# HVAC8V2.net
KiCad netlist of a schematic drawn in EAGLE
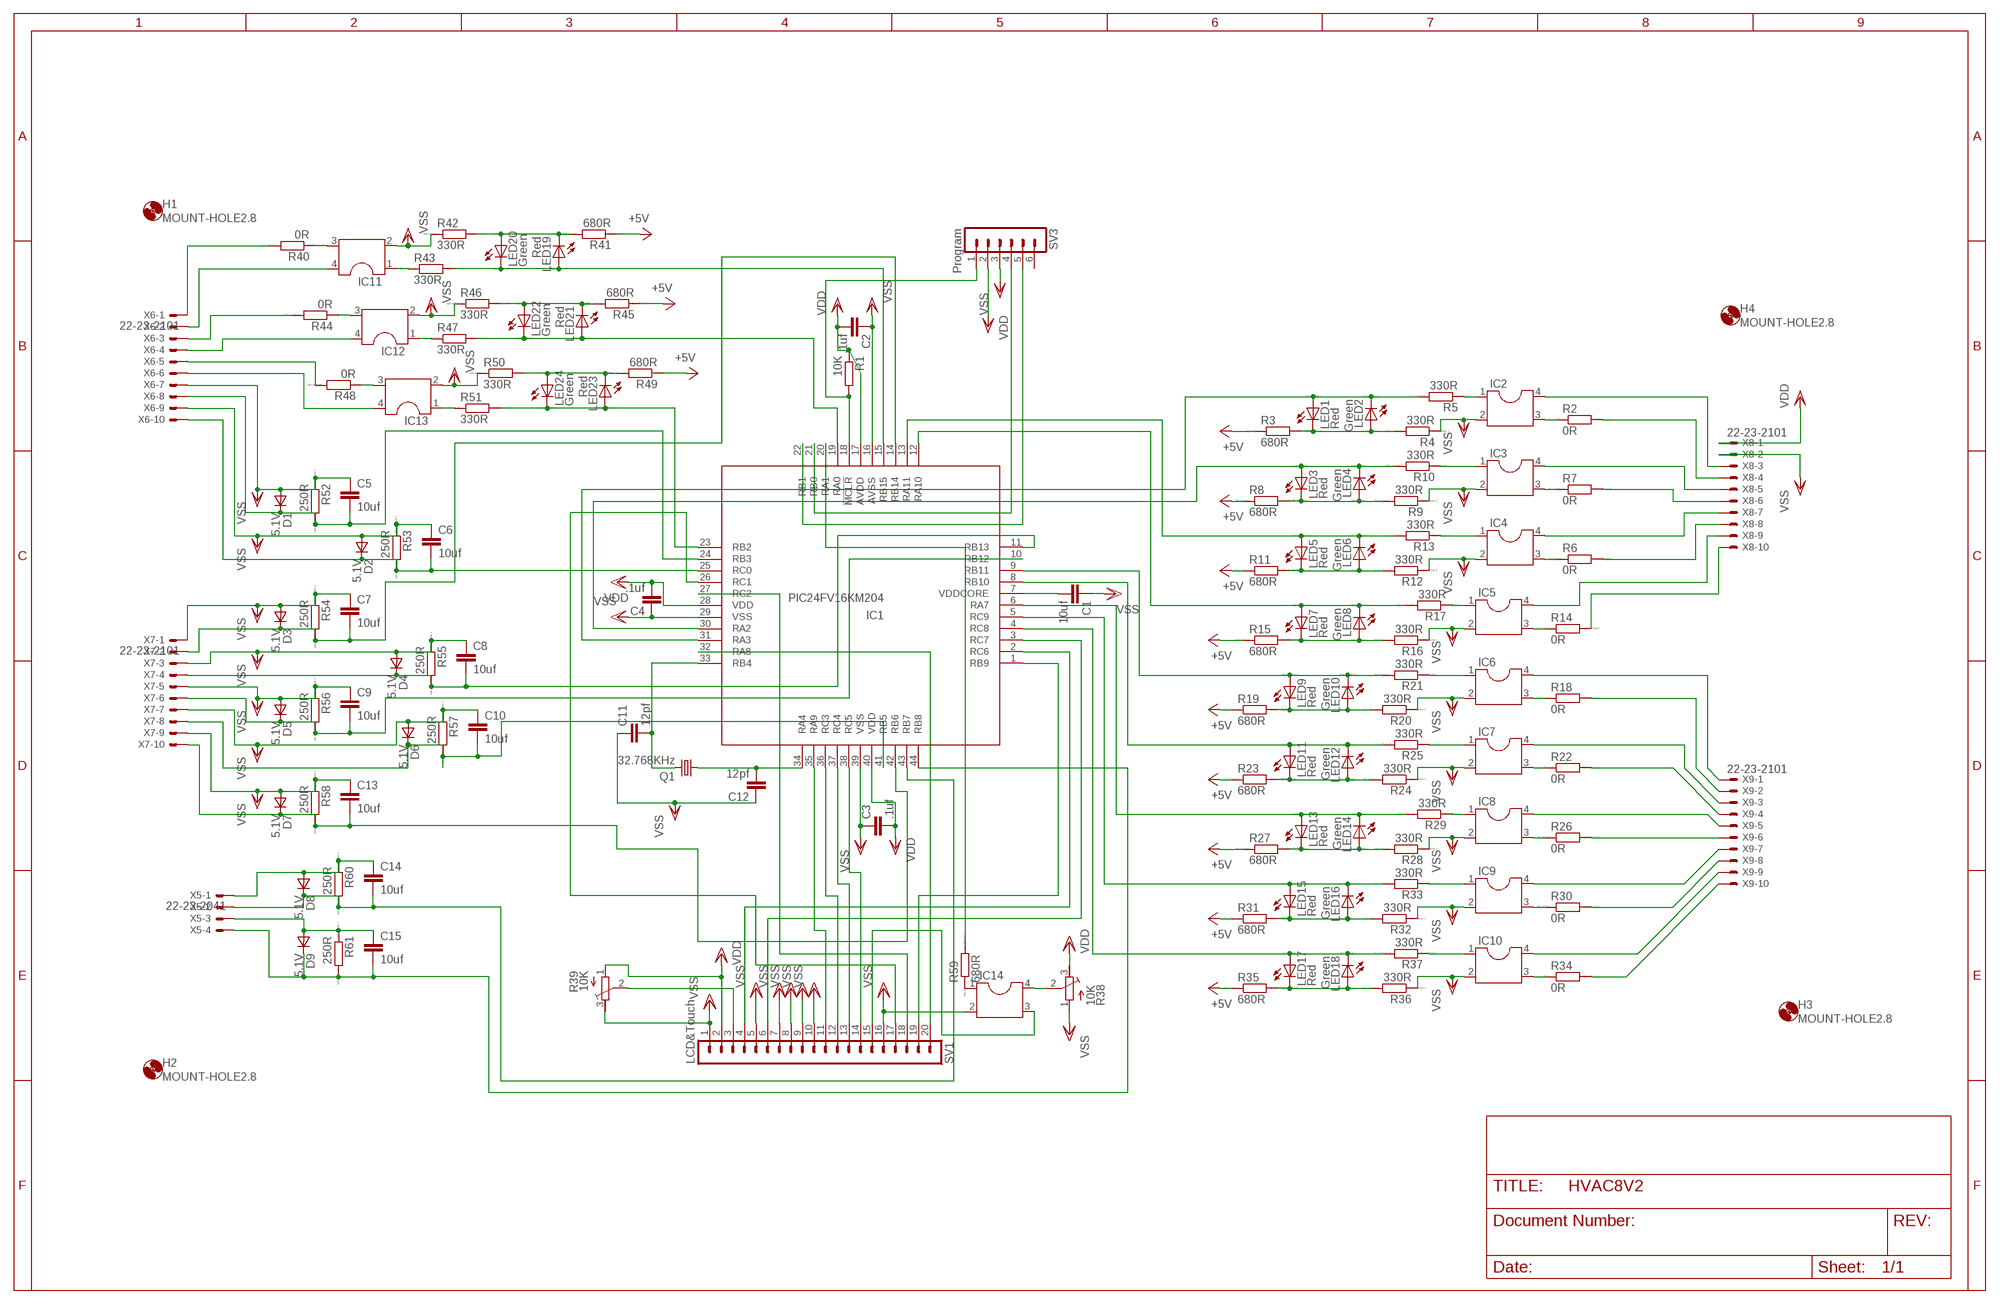
[diagram p0: schematic, sheet 1]

(export (version "E")
  (design (tool "Eeschema 10.0.6"))
  (components
    (comp (ref "C1")
      (value "10uf")
      (footprint "eagle-import:C1206")
      (libsource (lib "eagle-import") (part "C-EUC1206"))
    )
    (comp (ref "C2")
      (value ".1uf")
      (footprint "eagle-import:C1206")
      (libsource (lib "eagle-import") (part "C-EUC1206"))
    )
    (comp (ref "C3")
      (value ".1uf")
      (footprint "eagle-import:C1206")
      (libsource (lib "eagle-import") (part "C-EUC1206"))
    )
    (comp (ref "C4")
      (value ".1uf")
      (footprint "eagle-import:C1206")
      (libsource (lib "eagle-import") (part "C-EUC1206"))
    )
    (comp (ref "C5")
      (value "10uf")
      (footprint "eagle-import:C1206")
      (libsource (lib "eagle-import") (part "C-EUC1206"))
    )
    (comp (ref "C6")
      (value "10uf")
      (footprint "eagle-import:C1206")
      (libsource (lib "eagle-import") (part "C-EUC1206"))
    )
    (comp (ref "C7")
      (value "10uf")
      (footprint "eagle-import:C1206")
      (libsource (lib "eagle-import") (part "C-EUC1206"))
    )
    (comp (ref "C8")
      (value "10uf")
      (footprint "eagle-import:C1206")
      (libsource (lib "eagle-import") (part "C-EUC1206"))
    )
    (comp (ref "C9")
      (value "10uf")
      (footprint "eagle-import:C1206")
      (libsource (lib "eagle-import") (part "C-EUC1206"))
    )
    (comp (ref "C10")
      (value "10uf")
      (footprint "eagle-import:C1206")
      (libsource (lib "eagle-import") (part "C-EUC1206"))
    )
    (comp (ref "C11")
      (value "12pf")
      (footprint "eagle-import:C0603")
      (libsource (lib "eagle-import") (part "C-EUC0603"))
    )
    (comp (ref "C12")
      (value "12pf")
      (footprint "eagle-import:C0603")
      (libsource (lib "eagle-import") (part "C-EUC0603"))
    )
    (comp (ref "C13")
      (value "10uf")
      (footprint "eagle-import:C1206")
      (libsource (lib "eagle-import") (part "C-EUC1206"))
    )
    (comp (ref "C14")
      (value "10uf")
      (footprint "eagle-import:C1206")
      (libsource (lib "eagle-import") (part "C-EUC1206"))
    )
    (comp (ref "C15")
      (value "10uf")
      (footprint "eagle-import:C1206")
      (libsource (lib "eagle-import") (part "C-EUC1206"))
    )
    (comp (ref "D1")
      (value "5.1V")
      (footprint "eagle-import:SOD323")
      (fields (field (name "MPN") "CDSOD323-T05C"))
      (libsource (lib "eagle-import") (part "DSOD323"))
    )
    (comp (ref "D2")
      (value "5.1V")
      (footprint "eagle-import:SOD323")
      (fields (field (name "MPN") "CDSOD323-T05C"))
      (libsource (lib "eagle-import") (part "DSOD323"))
    )
    (comp (ref "D3")
      (value "5.1V")
      (footprint "eagle-import:SOD323")
      (fields (field (name "MPN") "CDSOD323-T05C"))
      (libsource (lib "eagle-import") (part "DSOD323"))
    )
    (comp (ref "D4")
      (value "5.1V")
      (footprint "eagle-import:SOD323")
      (fields (field (name "MPN") "CDSOD323-T05C"))
      (libsource (lib "eagle-import") (part "DSOD323"))
    )
    (comp (ref "D5")
      (value "5.1V")
      (footprint "eagle-import:SOD323")
      (fields (field (name "MPN") "CDSOD323-T05C"))
      (libsource (lib "eagle-import") (part "DSOD323"))
    )
    (comp (ref "D6")
      (value "5.1V")
      (footprint "eagle-import:SOD323")
      (fields (field (name "MPN") "CDSOD323-T05C"))
      (libsource (lib "eagle-import") (part "DSOD323"))
    )
    (comp (ref "D7")
      (value "5.1V")
      (footprint "eagle-import:SOD323")
      (fields (field (name "MPN") "CDSOD323-T05C"))
      (libsource (lib "eagle-import") (part "DSOD323"))
    )
    (comp (ref "D8")
      (value "5.1V")
      (footprint "eagle-import:SOD323")
      (fields (field (name "MPN") "CDSOD323-T05C"))
      (libsource (lib "eagle-import") (part "DSOD323"))
    )
    (comp (ref "D9")
      (value "5.1V")
      (footprint "eagle-import:SOD323")
      (fields (field (name "MPN") "CDSOD323-T05C"))
      (libsource (lib "eagle-import") (part "DSOD323"))
    )
    (comp (ref "H1")
      (value "MOUNT-HOLE2.8")
      (footprint "eagle-import:2,8")
      (libsource (lib "eagle-import") (part "MOUNT-HOLE2.8"))
    )
    (comp (ref "H2")
      (value "MOUNT-HOLE2.8")
      (footprint "eagle-import:2,8")
      (libsource (lib "eagle-import") (part "MOUNT-HOLE2.8"))
    )
    (comp (ref "H3")
      (value "MOUNT-HOLE2.8")
      (footprint "eagle-import:2,8")
      (libsource (lib "eagle-import") (part "MOUNT-HOLE2.8"))
    )
    (comp (ref "H4")
      (value "MOUNT-HOLE2.8")
      (footprint "eagle-import:2,8")
      (libsource (lib "eagle-import") (part "MOUNT-HOLE2.8"))
    )
    (comp (ref "IC1")
      (value "PIC24FV16KM204")
      (footprint "eagle-import:TQFP44")
      (libsource (lib "eagle-import") (part "PIC24FV16KM204"))
    )
    (comp (ref "IC2")
      (value "DIL4S")
      (footprint "eagle-import:SOCKET-04")
      (libsource (lib "eagle-import") (part "DIL4S"))
    )
    (comp (ref "IC3")
      (value "DIL4S")
      (footprint "eagle-import:SOCKET-04")
      (libsource (lib "eagle-import") (part "DIL4S"))
    )
    (comp (ref "IC4")
      (value "DIL4S")
      (footprint "eagle-import:SOCKET-04")
      (libsource (lib "eagle-import") (part "DIL4S"))
    )
    (comp (ref "IC5")
      (value "DIL4S")
      (footprint "eagle-import:SOCKET-04")
      (libsource (lib "eagle-import") (part "DIL4S"))
    )
    (comp (ref "IC6")
      (value "DIL4S")
      (footprint "eagle-import:SOCKET-04")
      (libsource (lib "eagle-import") (part "DIL4S"))
    )
    (comp (ref "IC7")
      (value "DIL4S")
      (footprint "eagle-import:SOCKET-04")
      (libsource (lib "eagle-import") (part "DIL4S"))
    )
    (comp (ref "IC8")
      (value "DIL4S")
      (footprint "eagle-import:SOCKET-04")
      (libsource (lib "eagle-import") (part "DIL4S"))
    )
    (comp (ref "IC9")
      (value "DIL4S")
      (footprint "eagle-import:SOCKET-04")
      (libsource (lib "eagle-import") (part "DIL4S"))
    )
    (comp (ref "IC10")
      (value "DIL4S")
      (footprint "eagle-import:SOCKET-04")
      (libsource (lib "eagle-import") (part "DIL4S"))
    )
    (comp (ref "IC11")
      (value "DIL4S")
      (footprint "eagle-import:SOCKET-04")
      (libsource (lib "eagle-import") (part "DIL4S"))
    )
    (comp (ref "IC12")
      (value "DIL4S")
      (footprint "eagle-import:SOCKET-04")
      (libsource (lib "eagle-import") (part "DIL4S"))
    )
    (comp (ref "IC13")
      (value "DIL4S")
      (footprint "eagle-import:SOCKET-04")
      (libsource (lib "eagle-import") (part "DIL4S"))
    )
    (comp (ref "IC14")
      (value "DIL4S")
      (footprint "eagle-import:SOCKET-04")
      (libsource (lib "eagle-import") (part "DIL4S"))
    )
    (comp (ref "LED1")
      (value "Red")
      (footprint "eagle-import:LED_1206")
      (libsource (lib "eagle-import") (part "LED_E"))
    )
    (comp (ref "LED2")
      (value "Green")
      (footprint "eagle-import:LED_1206")
      (libsource (lib "eagle-import") (part "LED_E"))
    )
    (comp (ref "LED3")
      (value "Red")
      (footprint "eagle-import:LED_1206")
      (libsource (lib "eagle-import") (part "LED_E"))
    )
    (comp (ref "LED4")
      (value "Green")
      (footprint "eagle-import:LED_1206")
      (libsource (lib "eagle-import") (part "LED_E"))
    )
    (comp (ref "LED5")
      (value "Red")
      (footprint "eagle-import:LED_1206")
      (libsource (lib "eagle-import") (part "LED_E"))
    )
    (comp (ref "LED6")
      (value "Green")
      (footprint "eagle-import:LED_1206")
      (libsource (lib "eagle-import") (part "LED_E"))
    )
    (comp (ref "LED7")
      (value "Red")
      (footprint "eagle-import:LED_1206")
      (libsource (lib "eagle-import") (part "LED_E"))
    )
    (comp (ref "LED8")
      (value "Green")
      (footprint "eagle-import:LED_1206")
      (libsource (lib "eagle-import") (part "LED_E"))
    )
    (comp (ref "LED9")
      (value "Red")
      (footprint "eagle-import:LED_1206")
      (libsource (lib "eagle-import") (part "LED_E"))
    )
    (comp (ref "LED10")
      (value "Green")
      (footprint "eagle-import:LED_1206")
      (libsource (lib "eagle-import") (part "LED_E"))
    )
    (comp (ref "LED11")
      (value "Red")
      (footprint "eagle-import:LED_1206")
      (libsource (lib "eagle-import") (part "LED_E"))
    )
    (comp (ref "LED12")
      (value "Green")
      (footprint "eagle-import:LED_1206")
      (libsource (lib "eagle-import") (part "LED_E"))
    )
    (comp (ref "LED13")
      (value "Red")
      (footprint "eagle-import:LED_1206")
      (libsource (lib "eagle-import") (part "LED_E"))
    )
    (comp (ref "LED14")
      (value "Green")
      (footprint "eagle-import:LED_1206")
      (libsource (lib "eagle-import") (part "LED_E"))
    )
    (comp (ref "LED15")
      (value "Red")
      (footprint "eagle-import:LED_1206")
      (libsource (lib "eagle-import") (part "LED_E"))
    )
    (comp (ref "LED16")
      (value "Green")
      (footprint "eagle-import:LED_1206")
      (libsource (lib "eagle-import") (part "LED_E"))
    )
    (comp (ref "LED17")
      (value "Red")
      (footprint "eagle-import:LED_1206")
      (libsource (lib "eagle-import") (part "LED_E"))
    )
    (comp (ref "LED18")
      (value "Green")
      (footprint "eagle-import:LED_1206")
      (libsource (lib "eagle-import") (part "LED_E"))
    )
    (comp (ref "LED19")
      (value "Red")
      (footprint "eagle-import:LED_1206")
      (libsource (lib "eagle-import") (part "LED_E"))
    )
    (comp (ref "LED20")
      (value "Green")
      (footprint "eagle-import:LED_1206")
      (libsource (lib "eagle-import") (part "LED_E"))
    )
    (comp (ref "LED21")
      (value "Red")
      (footprint "eagle-import:LED_1206")
      (libsource (lib "eagle-import") (part "LED_E"))
    )
    (comp (ref "LED22")
      (value "Green")
      (footprint "eagle-import:LED_1206")
      (libsource (lib "eagle-import") (part "LED_E"))
    )
    (comp (ref "LED23")
      (value "Red")
      (footprint "eagle-import:LED_1206")
      (libsource (lib "eagle-import") (part "LED_E"))
    )
    (comp (ref "LED24")
      (value "Green")
      (footprint "eagle-import:LED_1206")
      (libsource (lib "eagle-import") (part "LED_E"))
    )
    (comp (ref "Q1")
      (value "32.768KHz")
      (footprint "eagle-import:TC26H")
      (libsource (lib "eagle-import") (part "CRYSTALTC26H"))
    )
    (comp (ref "R1")
      (value "10K")
      (footprint "eagle-import:R1206")
      (libsource (lib "eagle-import") (part "R-EU_R1206"))
    )
    (comp (ref "R2")
      (value "0R")
      (footprint "eagle-import:R1206")
      (libsource (lib "eagle-import") (part "RR1206"))
    )
    (comp (ref "R3")
      (value "680R")
      (footprint "eagle-import:R1206")
      (libsource (lib "eagle-import") (part "RR1206"))
    )
    (comp (ref "R4")
      (value "330R")
      (footprint "eagle-import:R1206")
      (libsource (lib "eagle-import") (part "RR1206"))
    )
    (comp (ref "R5")
      (value "330R")
      (footprint "eagle-import:R1206")
      (libsource (lib "eagle-import") (part "RR1206"))
    )
    (comp (ref "R6")
      (value "0R")
      (footprint "eagle-import:R1206")
      (libsource (lib "eagle-import") (part "RR1206"))
    )
    (comp (ref "R7")
      (value "0R")
      (footprint "eagle-import:R1206")
      (libsource (lib "eagle-import") (part "RR1206"))
    )
    (comp (ref "R8")
      (value "680R")
      (footprint "eagle-import:R1206")
      (libsource (lib "eagle-import") (part "RR1206"))
    )
    (comp (ref "R9")
      (value "330R")
      (footprint "eagle-import:R1206")
      (libsource (lib "eagle-import") (part "RR1206"))
    )
    (comp (ref "R10")
      (value "330R")
      (footprint "eagle-import:R1206")
      (libsource (lib "eagle-import") (part "RR1206"))
    )
    (comp (ref "R11")
      (value "680R")
      (footprint "eagle-import:R1206")
      (libsource (lib "eagle-import") (part "RR1206"))
    )
    (comp (ref "R12")
      (value "330R")
      (footprint "eagle-import:R1206")
      (libsource (lib "eagle-import") (part "RR1206"))
    )
    (comp (ref "R13")
      (value "330R")
      (footprint "eagle-import:R1206")
      (libsource (lib "eagle-import") (part "RR1206"))
    )
    (comp (ref "R14")
      (value "0R")
      (footprint "eagle-import:R1206")
      (libsource (lib "eagle-import") (part "RR1206"))
    )
    (comp (ref "R15")
      (value "680R")
      (footprint "eagle-import:R1206")
      (libsource (lib "eagle-import") (part "RR1206"))
    )
    (comp (ref "R16")
      (value "330R")
      (footprint "eagle-import:R1206")
      (libsource (lib "eagle-import") (part "RR1206"))
    )
    (comp (ref "R17")
      (value "330R")
      (footprint "eagle-import:R1206")
      (libsource (lib "eagle-import") (part "RR1206"))
    )
    (comp (ref "R18")
      (value "0R")
      (footprint "eagle-import:R1206")
      (libsource (lib "eagle-import") (part "RR1206"))
    )
    (comp (ref "R19")
      (value "680R")
      (footprint "eagle-import:R1206")
      (libsource (lib "eagle-import") (part "RR1206"))
    )
    (comp (ref "R20")
      (value "330R")
      (footprint "eagle-import:R1206")
      (libsource (lib "eagle-import") (part "RR1206"))
    )
    (comp (ref "R21")
      (value "330R")
      (footprint "eagle-import:R1206")
      (libsource (lib "eagle-import") (part "RR1206"))
    )
    (comp (ref "R22")
      (value "0R")
      (footprint "eagle-import:R1206")
      (libsource (lib "eagle-import") (part "RR1206"))
    )
    (comp (ref "R23")
      (value "680R")
      (footprint "eagle-import:R1206")
      (libsource (lib "eagle-import") (part "RR1206"))
    )
    (comp (ref "R24")
      (value "330R")
      (footprint "eagle-import:R1206")
      (libsource (lib "eagle-import") (part "RR1206"))
    )
    (comp (ref "R25")
      (value "330R")
      (footprint "eagle-import:R1206")
      (libsource (lib "eagle-import") (part "RR1206"))
    )
    (comp (ref "R26")
      (value "0R")
      (footprint "eagle-import:R1206")
      (libsource (lib "eagle-import") (part "RR1206"))
    )
    (comp (ref "R27")
      (value "680R")
      (footprint "eagle-import:R1206")
      (libsource (lib "eagle-import") (part "RR1206"))
    )
    (comp (ref "R28")
      (value "330R")
      (footprint "eagle-import:R1206")
      (libsource (lib "eagle-import") (part "RR1206"))
    )
    (comp (ref "R29")
      (value "330R")
      (footprint "eagle-import:R1206")
      (libsource (lib "eagle-import") (part "RR1206"))
    )
    (comp (ref "R30")
      (value "0R")
      (footprint "eagle-import:R1206")
      (libsource (lib "eagle-import") (part "RR1206"))
    )
    (comp (ref "R31")
      (value "680R")
      (footprint "eagle-import:R1206")
      (libsource (lib "eagle-import") (part "RR1206"))
    )
    (comp (ref "R32")
      (value "330R")
      (footprint "eagle-import:R1206")
      (libsource (lib "eagle-import") (part "RR1206"))
    )
    (comp (ref "R33")
      (value "330R")
      (footprint "eagle-import:R1206")
      (libsource (lib "eagle-import") (part "RR1206"))
    )
    (comp (ref "R34")
      (value "0R")
      (footprint "eagle-import:R1206")
      (libsource (lib "eagle-import") (part "RR1206"))
    )
    (comp (ref "R35")
      (value "680R")
      (footprint "eagle-import:R1206")
      (libsource (lib "eagle-import") (part "RR1206"))
    )
    (comp (ref "R36")
      (value "330R")
      (footprint "eagle-import:R1206")
      (libsource (lib "eagle-import") (part "RR1206"))
    )
    (comp (ref "R37")
      (value "330R")
      (footprint "eagle-import:R1206")
      (libsource (lib "eagle-import") (part "RR1206"))
    )
    (comp (ref "R38")
      (value "10K")
      (footprint "eagle-import:RTRIM3296W")
      (libsource (lib "eagle-import") (part "R-TRIMM3296W"))
    )
    (comp (ref "R39")
      (value "10K")
      (footprint "eagle-import:RTRIM3296W")
      (libsource (lib "eagle-import") (part "R-TRIMM3296W"))
    )
    (comp (ref "R40")
      (value "0R")
      (footprint "eagle-import:R1206")
      (libsource (lib "eagle-import") (part "RR1206"))
    )
    (comp (ref "R41")
      (value "680R")
      (footprint "eagle-import:R1206")
      (libsource (lib "eagle-import") (part "RR1206"))
    )
    (comp (ref "R42")
      (value "330R")
      (footprint "eagle-import:R1206")
      (libsource (lib "eagle-import") (part "RR1206"))
    )
    (comp (ref "R43")
      (value "330R")
      (footprint "eagle-import:R1206")
      (libsource (lib "eagle-import") (part "RR1206"))
    )
    (comp (ref "R44")
      (value "0R")
      (footprint "eagle-import:R1206")
      (libsource (lib "eagle-import") (part "RR1206"))
    )
    (comp (ref "R45")
      (value "680R")
      (footprint "eagle-import:R1206")
      (libsource (lib "eagle-import") (part "RR1206"))
    )
    (comp (ref "R46")
      (value "330R")
      (footprint "eagle-import:R1206")
      (libsource (lib "eagle-import") (part "RR1206"))
    )
    (comp (ref "R47")
      (value "330R")
      (footprint "eagle-import:R1206")
      (libsource (lib "eagle-import") (part "RR1206"))
    )
    (comp (ref "R48")
      (value "0R")
      (footprint "eagle-import:R1206")
      (libsource (lib "eagle-import") (part "RR1206"))
    )
    (comp (ref "R49")
      (value "680R")
      (footprint "eagle-import:R1206")
      (libsource (lib "eagle-import") (part "RR1206"))
    )
    (comp (ref "R50")
      (value "330R")
      (footprint "eagle-import:R1206")
      (libsource (lib "eagle-import") (part "RR1206"))
    )
    (comp (ref "R51")
      (value "330R")
      (footprint "eagle-import:R1206")
      (libsource (lib "eagle-import") (part "RR1206"))
    )
    (comp (ref "R52")
      (value "250R")
      (footprint "eagle-import:R1206")
      (libsource (lib "eagle-import") (part "RR1206"))
    )
    (comp (ref "R53")
      (value "250R")
      (footprint "eagle-import:R1206")
      (libsource (lib "eagle-import") (part "RR1206"))
    )
    (comp (ref "R54")
      (value "250R")
      (footprint "eagle-import:R1206")
      (libsource (lib "eagle-import") (part "RR1206"))
    )
    (comp (ref "R55")
      (value "250R")
      (footprint "eagle-import:R1206")
      (libsource (lib "eagle-import") (part "RR1206"))
    )
    (comp (ref "R56")
      (value "250R")
      (footprint "eagle-import:R1206")
      (libsource (lib "eagle-import") (part "RR1206"))
    )
    (comp (ref "R57")
      (value "250R")
      (footprint "eagle-import:R1206")
      (libsource (lib "eagle-import") (part "RR1206"))
    )
    (comp (ref "R58")
      (value "250R")
      (footprint "eagle-import:R1206")
      (libsource (lib "eagle-import") (part "RR1206"))
    )
    (comp (ref "R59")
      (value "680R")
      (footprint "eagle-import:R1206")
      (libsource (lib "eagle-import") (part "RR1206"))
    )
    (comp (ref "R60")
      (value "250R")
      (footprint "eagle-import:R1206")
      (libsource (lib "eagle-import") (part "RR1206"))
    )
    (comp (ref "R61")
      (value "250R")
      (footprint "eagle-import:R1206")
      (libsource (lib "eagle-import") (part "RR1206"))
    )
    (comp (ref "SV1")
      (value "LCD&Touch")
      (footprint "eagle-import:MA20-1")
      (libsource (lib "eagle-import") (part "MA20-1"))
    )
    (comp (ref "SV3")
      (value "Program")
      (footprint "eagle-import:MA06-1")
      (libsource (lib "eagle-import") (part "MA06-1"))
    )
    (comp (ref "X5")
      (value "22-23-2041")
      (footprint "eagle-import:22-23-2041")
      (fields (field (name "MF") "MOLEX"))
      (libsource (lib "eagle-import") (part "22-23-2041"))
    )
    (comp (ref "X6")
      (value "22-23-2101")
      (footprint "eagle-import:22-23-2101")
      (fields (field (name "MF") "MOLEX"))
      (libsource (lib "eagle-import") (part "22-23-2101"))
    )
    (comp (ref "X7")
      (value "22-23-2101")
      (footprint "eagle-import:22-23-2101")
      (fields (field (name "MF") "MOLEX"))
      (libsource (lib "eagle-import") (part "22-23-2101"))
    )
    (comp (ref "X8")
      (value "22-23-2101")
      (footprint "eagle-import:22-23-2101")
      (fields (field (name "MF") "MOLEX"))
      (libsource (lib "eagle-import") (part "22-23-2101"))
    )
    (comp (ref "X9")
      (value "22-23-2101")
      (footprint "eagle-import:22-23-2101")
      (fields (field (name "MF") "MOLEX"))
      (libsource (lib "eagle-import") (part "22-23-2101"))
    )
  )
  (nets
    (net (code "1") (name "+5V") (class "Default")
      (node (ref "R11") (pin "1") (pinfunction "1_1") (pintype "passive"))
      (node (ref "R15") (pin "1") (pinfunction "1_1") (pintype "passive"))
      (node (ref "R19") (pin "1") (pinfunction "1_1") (pintype "passive"))
      (node (ref "R23") (pin "1") (pinfunction "1_1") (pintype "passive"))
      (node (ref "R27") (pin "1") (pinfunction "1_1") (pintype "passive"))
      (node (ref "R3") (pin "1") (pinfunction "1_1") (pintype "passive"))
      (node (ref "R31") (pin "1") (pinfunction "1_1") (pintype "passive"))
      (node (ref "R35") (pin "1") (pinfunction "1_1") (pintype "passive"))
      (node (ref "R41") (pin "1") (pinfunction "1_1") (pintype "passive"))
      (node (ref "R45") (pin "1") (pinfunction "1_1") (pintype "passive"))
      (node (ref "R49") (pin "1") (pinfunction "1_1") (pintype "passive"))
      (node (ref "R8") (pin "1") (pinfunction "1_1") (pintype "passive"))
    )
    (net (code "2") (name "Net-(D1-C)") (class "Default")
      (node (ref "C5") (pin "2") (pinfunction "2_2") (pintype "passive"))
      (node (ref "D1") (pin "1") (pinfunction "C_1") (pintype "passive"))
      (node (ref "IC1") (pin "24") (pinfunction "RB3_24") (pintype "bidirectional"))
      (node (ref "R52") (pin "2") (pinfunction "2_2") (pintype "passive"))
      (node (ref "X6") (pin "8") (pinfunction "S_8") (pintype "passive"))
    )
    (net (code "3") (name "Net-(D2-C)") (class "Default")
      (node (ref "C6") (pin "2") (pinfunction "2_2") (pintype "passive"))
      (node (ref "D2") (pin "1") (pinfunction "C_1") (pintype "passive"))
      (node (ref "IC1") (pin "25") (pinfunction "RC0_25") (pintype "bidirectional"))
      (node (ref "R53") (pin "2") (pinfunction "2_2") (pintype "passive"))
      (node (ref "X6") (pin "10") (pinfunction "S_10") (pintype "passive"))
    )
    (net (code "4") (name "Net-(D3-C)") (class "Default")
      (node (ref "C7") (pin "2") (pinfunction "2_2") (pintype "passive"))
      (node (ref "D3") (pin "1") (pinfunction "C_1") (pintype "passive"))
      (node (ref "IC1") (pin "14") (pinfunction "RB14_14") (pintype "bidirectional"))
      (node (ref "R54") (pin "2") (pinfunction "2_2") (pintype "passive"))
      (node (ref "X7") (pin "2") (pinfunction "S_2") (pintype "passive"))
    )
    (net (code "5") (name "Net-(D4-C)") (class "Default")
      (node (ref "C8") (pin "2") (pinfunction "2_2") (pintype "passive"))
      (node (ref "D4") (pin "1") (pinfunction "C_1") (pintype "passive"))
      (node (ref "IC1") (pin "11") (pinfunction "RB13_11") (pintype "bidirectional"))
      (node (ref "R55") (pin "2") (pinfunction "2_2") (pintype "passive"))
      (node (ref "X7") (pin "4") (pinfunction "S_4") (pintype "passive"))
    )
    (net (code "6") (name "Net-(D5-C)") (class "Default")
      (node (ref "C9") (pin "2") (pinfunction "2_2") (pintype "passive"))
      (node (ref "D5") (pin "1") (pinfunction "C_1") (pintype "passive"))
      (node (ref "IC1") (pin "10") (pinfunction "RB12_10") (pintype "bidirectional"))
      (node (ref "R56") (pin "2") (pinfunction "2_2") (pintype "passive"))
      (node (ref "X7") (pin "6") (pinfunction "S_6") (pintype "passive"))
    )
    (net (code "7") (name "Net-(D6-C)") (class "Default")
      (node (ref "C10") (pin "2") (pinfunction "2_2") (pintype "passive"))
      (node (ref "D6") (pin "1") (pinfunction "C_1") (pintype "passive"))
      (node (ref "IC1") (pin "41") (pinfunction "RB5_41") (pintype "bidirectional"))
      (node (ref "R57") (pin "2") (pinfunction "2_2") (pintype "passive"))
      (node (ref "X7") (pin "8") (pinfunction "S_8") (pintype "passive"))
    )
    (net (code "8") (name "Net-(D7-C)") (class "Default")
      (node (ref "C13") (pin "2") (pinfunction "2_2") (pintype "passive"))
      (node (ref "D7") (pin "1") (pinfunction "C_1") (pintype "passive"))
      (node (ref "IC1") (pin "42") (pinfunction "RB6_42") (pintype "bidirectional"))
      (node (ref "R58") (pin "2") (pinfunction "2_2") (pintype "passive"))
      (node (ref "X7") (pin "10") (pinfunction "S_10") (pintype "passive"))
    )
    (net (code "9") (name "Net-(D8-A)") (class "Default")
      (node (ref "C14") (pin "1") (pinfunction "1_1") (pintype "passive"))
      (node (ref "D8") (pin "2") (pinfunction "A_2") (pintype "passive"))
      (node (ref "R60") (pin "1") (pinfunction "1_1") (pintype "passive"))
      (node (ref "X5") (pin "1") (pinfunction "S_1") (pintype "passive"))
    )
    (net (code "10") (name "Net-(D8-C)") (class "Default")
      (node (ref "C14") (pin "2") (pinfunction "2_2") (pintype "passive"))
      (node (ref "D8") (pin "1") (pinfunction "C_1") (pintype "passive"))
      (node (ref "IC1") (pin "43") (pinfunction "RB7_43") (pintype "bidirectional"))
      (node (ref "R60") (pin "2") (pinfunction "2_2") (pintype "passive"))
      (node (ref "X5") (pin "2") (pinfunction "S_2") (pintype "passive"))
    )
    (net (code "11") (name "Net-(D9-A)") (class "Default")
      (node (ref "C15") (pin "1") (pinfunction "1_1") (pintype "passive"))
      (node (ref "D9") (pin "2") (pinfunction "A_2") (pintype "passive"))
      (node (ref "R61") (pin "1") (pinfunction "1_1") (pintype "passive"))
      (node (ref "X5") (pin "3") (pinfunction "S_3") (pintype "passive"))
    )
    (net (code "12") (name "Net-(D9-C)") (class "Default")
      (node (ref "C15") (pin "2") (pinfunction "2_2") (pintype "passive"))
      (node (ref "D9") (pin "1") (pinfunction "C_1") (pintype "passive"))
      (node (ref "IC1") (pin "44") (pinfunction "RB8_44") (pintype "bidirectional"))
      (node (ref "R61") (pin "2") (pinfunction "2_2") (pintype "passive"))
      (node (ref "X5") (pin "4") (pinfunction "S_4") (pintype "passive"))
    )
    (net (code "13") (name "Net-(IC1-RA0)") (class "Default")
      (node (ref "IC1") (pin "19") (pinfunction "RA0_19") (pintype "bidirectional"))
      (node (ref "LED21") (pin "A") (pinfunction "A_A") (pintype "passive"))
      (node (ref "LED22") (pin "C") (pinfunction "C_C") (pintype "passive"))
      (node (ref "R47") (pin "2") (pinfunction "2_2") (pintype "passive"))
    )
    (net (code "14") (name "Net-(IC1-RA1)") (class "Default")
      (node (ref "IC1") (pin "20") (pinfunction "RA1_20") (pintype "bidirectional"))
      (node (ref "R59") (pin "2") (pinfunction "2_2") (pintype "passive"))
    )
    (net (code "15") (name "Net-(IC1-RA2)") (class "Default")
      (node (ref "IC1") (pin "30") (pinfunction "RA2_30") (pintype "bidirectional"))
      (node (ref "LED3") (pin "A") (pinfunction "A_A") (pintype "passive"))
      (node (ref "LED4") (pin "C") (pinfunction "C_C") (pintype "passive"))
      (node (ref "R10") (pin "2") (pinfunction "2_2") (pintype "passive"))
    )
    (net (code "16") (name "Net-(IC1-RA3)") (class "Default")
      (node (ref "IC1") (pin "31") (pinfunction "RA3_31") (pintype "bidirectional"))
      (node (ref "LED1") (pin "A") (pinfunction "A_A") (pintype "passive"))
      (node (ref "LED2") (pin "C") (pinfunction "C_C") (pintype "passive"))
      (node (ref "R5") (pin "2") (pinfunction "2_2") (pintype "passive"))
    )
    (net (code "17") (name "Net-(IC1-RA4)") (class "Default")
      (node (ref "C12") (pin "2") (pinfunction "2_2") (pintype "passive"))
      (node (ref "IC1") (pin "34") (pinfunction "RA4_34") (pintype "bidirectional"))
      (node (ref "Q1") (pin "1") (pinfunction "1_1") (pintype "passive"))
    )
    (net (code "18") (name "Net-(IC1-RA7)") (class "Default")
      (node (ref "IC1") (pin "6") (pinfunction "RA7_6") (pintype "bidirectional"))
      (node (ref "LED13") (pin "A") (pinfunction "A_A") (pintype "passive"))
      (node (ref "LED14") (pin "C") (pinfunction "C_C") (pintype "passive"))
      (node (ref "R29") (pin "2") (pinfunction "2_2") (pintype "passive"))
    )
    (net (code "19") (name "Net-(IC1-RA8)") (class "Default")
      (node (ref "IC1") (pin "32") (pinfunction "RA8_32") (pintype "bidirectional"))
      (node (ref "SV1") (pin "20") (pinfunction "20_20") (pintype "passive"))
    )
    (net (code "20") (name "Net-(IC1-RA9)") (class "Default")
      (node (ref "IC1") (pin "35") (pinfunction "RA9_35") (pintype "bidirectional"))
      (node (ref "SV1") (pin "11") (pinfunction "11_11") (pintype "passive"))
    )
    (net (code "21") (name "Net-(IC1-RA10)") (class "Default")
      (node (ref "IC1") (pin "12") (pinfunction "RA10_12") (pintype "bidirectional"))
      (node (ref "LED7") (pin "A") (pinfunction "A_A") (pintype "passive"))
      (node (ref "LED8") (pin "C") (pinfunction "C_C") (pintype "passive"))
      (node (ref "R17") (pin "2") (pinfunction "2_2") (pintype "passive"))
    )
    (net (code "22") (name "Net-(IC1-RA11)") (class "Default")
      (node (ref "IC1") (pin "13") (pinfunction "RA11_13") (pintype "bidirectional"))
      (node (ref "LED5") (pin "A") (pinfunction "A_A") (pintype "passive"))
      (node (ref "LED6") (pin "C") (pinfunction "C_C") (pintype "passive"))
      (node (ref "R13") (pin "2") (pinfunction "2_2") (pintype "passive"))
    )
    (net (code "23") (name "Net-(IC1-RB0)") (class "Default")
      (node (ref "IC1") (pin "21") (pinfunction "RB0_21") (pintype "bidirectional"))
      (node (ref "SV3") (pin "4") (pinfunction "4_4") (pintype "passive"))
    )
    (net (code "24") (name "Net-(IC1-RB1)") (class "Default")
      (node (ref "IC1") (pin "22") (pinfunction "RB1_22") (pintype "bidirectional"))
      (node (ref "SV3") (pin "5") (pinfunction "5_5") (pintype "passive"))
    )
    (net (code "25") (name "Net-(IC1-RB2)") (class "Default")
      (node (ref "IC1") (pin "23") (pinfunction "RB2_23") (pintype "bidirectional"))
      (node (ref "LED23") (pin "A") (pinfunction "A_A") (pintype "passive"))
      (node (ref "LED24") (pin "C") (pinfunction "C_C") (pintype "passive"))
      (node (ref "R51") (pin "2") (pinfunction "2_2") (pintype "passive"))
    )
    (net (code "26") (name "Net-(IC1-RB4)") (class "Default")
      (node (ref "C11") (pin "2") (pinfunction "2_2") (pintype "passive"))
      (node (ref "IC1") (pin "33") (pinfunction "RB4_33") (pintype "bidirectional"))
      (node (ref "Q1") (pin "2") (pinfunction "2_2") (pintype "passive"))
    )
    (net (code "27") (name "Net-(IC1-RB9)") (class "Default")
      (node (ref "IC1") (pin "1") (pinfunction "RB9_1") (pintype "bidirectional"))
      (node (ref "SV1") (pin "19") (pinfunction "19_19") (pintype "passive"))
    )
    (net (code "28") (name "Net-(IC1-RB10)") (class "Default")
      (node (ref "IC1") (pin "8") (pinfunction "RB10_8") (pintype "bidirectional"))
      (node (ref "LED11") (pin "A") (pinfunction "A_A") (pintype "passive"))
      (node (ref "LED12") (pin "C") (pinfunction "C_C") (pintype "passive"))
      (node (ref "R25") (pin "2") (pinfunction "2_2") (pintype "passive"))
    )
    (net (code "29") (name "Net-(IC1-RB11)") (class "Default")
      (node (ref "IC1") (pin "9") (pinfunction "RB11_9") (pintype "bidirectional"))
      (node (ref "LED10") (pin "C") (pinfunction "C_C") (pintype "passive"))
      (node (ref "LED9") (pin "A") (pinfunction "A_A") (pintype "passive"))
      (node (ref "R21") (pin "2") (pinfunction "2_2") (pintype "passive"))
    )
    (net (code "30") (name "Net-(IC1-RB15)") (class "Default")
      (node (ref "IC1") (pin "15") (pinfunction "RB15_15") (pintype "bidirectional"))
      (node (ref "LED19") (pin "A") (pinfunction "A_A") (pintype "passive"))
      (node (ref "LED20") (pin "C") (pinfunction "C_C") (pintype "passive"))
      (node (ref "R43") (pin "2") (pinfunction "2_2") (pintype "passive"))
    )
    (net (code "31") (name "Net-(IC1-RC1)") (class "Default")
      (node (ref "IC1") (pin "26") (pinfunction "RC1_26") (pintype "bidirectional"))
      (node (ref "SV1") (pin "17") (pinfunction "17_17") (pintype "passive"))
    )
    (net (code "32") (name "Net-(IC1-RC2)") (class "Default")
      (node (ref "IC1") (pin "27") (pinfunction "RC2_27") (pintype "bidirectional"))
      (node (ref "SV1") (pin "18") (pinfunction "18_18") (pintype "passive"))
    )
    (net (code "33") (name "Net-(IC1-RC3)") (class "Default")
      (node (ref "IC1") (pin "36") (pinfunction "RC3_36") (pintype "bidirectional"))
      (node (ref "SV1") (pin "12") (pinfunction "12_12") (pintype "passive"))
    )
    (net (code "34") (name "Net-(IC1-RC4)") (class "Default")
      (node (ref "IC1") (pin "37") (pinfunction "RC4_37") (pintype "bidirectional"))
      (node (ref "SV1") (pin "13") (pinfunction "13_13") (pintype "passive"))
    )
    (net (code "35") (name "Net-(IC1-RC5)") (class "Default")
      (node (ref "IC1") (pin "38") (pinfunction "RC5_38") (pintype "bidirectional"))
      (node (ref "SV1") (pin "14") (pinfunction "14_14") (pintype "passive"))
    )
    (net (code "36") (name "Net-(IC1-RC6)") (class "Default")
      (node (ref "IC1") (pin "2") (pinfunction "RC6_2") (pintype "bidirectional"))
      (node (ref "SV1") (pin "4") (pinfunction "4_4") (pintype "passive"))
    )
    (net (code "37") (name "Net-(IC1-RC7)") (class "Default")
      (node (ref "IC1") (pin "3") (pinfunction "RC7_3") (pintype "bidirectional"))
      (node (ref "SV1") (pin "6") (pinfunction "6_6") (pintype "passive"))
    )
    (net (code "38") (name "Net-(IC1-RC8)") (class "Default")
      (node (ref "IC1") (pin "4") (pinfunction "RC8_4") (pintype "bidirectional"))
      (node (ref "LED17") (pin "A") (pinfunction "A_A") (pintype "passive"))
      (node (ref "LED18") (pin "C") (pinfunction "C_C") (pintype "passive"))
      (node (ref "R37") (pin "2") (pinfunction "2_2") (pintype "passive"))
    )
    (net (code "39") (name "Net-(IC1-RC9)") (class "Default")
      (node (ref "IC1") (pin "5") (pinfunction "RC9_5") (pintype "bidirectional"))
      (node (ref "LED15") (pin "A") (pinfunction "A_A") (pintype "passive"))
      (node (ref "LED16") (pin "C") (pinfunction "C_C") (pintype "passive"))
      (node (ref "R33") (pin "2") (pinfunction "2_2") (pintype "passive"))
    )
    (net (code "40") (name "Net-(IC1-VDDCORE)") (class "Default")
      (node (ref "C1") (pin "2") (pinfunction "2_2") (pintype "passive"))
      (node (ref "IC1") (pin "7") (pinfunction "VDDCORE_7") (pintype "power_in"))
    )
    (net (code "41") (name "Net-(IC1-~{MCLR})") (class "Default")
      (node (ref "IC1") (pin "18") (pinfunction "~{MCLR}_18") (pintype "bidirectional"))
      (node (ref "R1") (pin "2") (pinfunction "2_2") (pintype "passive"))
      (node (ref "SV3") (pin "1") (pinfunction "1_1") (pintype "passive"))
    )
    (net (code "42") (name "Net-(IC2-Pad1)") (class "Default")
      (node (ref "IC2") (pin "1") (pinfunction "1_1") (pintype "passive"))
      (node (ref "R5") (pin "1") (pinfunction "1_1") (pintype "passive"))
    )
    (net (code "43") (name "Net-(IC2-Pad3)") (class "Default")
      (node (ref "IC2") (pin "3") (pinfunction "3_3") (pintype "passive"))
      (node (ref "R2") (pin "1") (pinfunction "1_1") (pintype "passive"))
    )
    (net (code "44") (name "Net-(IC3-Pad1)") (class "Default")
      (node (ref "IC3") (pin "1") (pinfunction "1_1") (pintype "passive"))
      (node (ref "R10") (pin "1") (pinfunction "1_1") (pintype "passive"))
    )
    (net (code "45") (name "Net-(IC3-Pad3)") (class "Default")
      (node (ref "IC3") (pin "3") (pinfunction "3_3") (pintype "passive"))
      (node (ref "R7") (pin "1") (pinfunction "1_1") (pintype "passive"))
    )
    (net (code "46") (name "Net-(IC4-Pad1)") (class "Default")
      (node (ref "IC4") (pin "1") (pinfunction "1_1") (pintype "passive"))
      (node (ref "R13") (pin "1") (pinfunction "1_1") (pintype "passive"))
    )
    (net (code "47") (name "Net-(IC4-Pad3)") (class "Default")
      (node (ref "IC4") (pin "3") (pinfunction "3_3") (pintype "passive"))
      (node (ref "R6") (pin "1") (pinfunction "1_1") (pintype "passive"))
    )
    (net (code "48") (name "Net-(IC5-Pad1)") (class "Default")
      (node (ref "IC5") (pin "1") (pinfunction "1_1") (pintype "passive"))
      (node (ref "R17") (pin "1") (pinfunction "1_1") (pintype "passive"))
    )
    (net (code "49") (name "Net-(IC5-Pad3)") (class "Default")
      (node (ref "IC5") (pin "3") (pinfunction "3_3") (pintype "passive"))
      (node (ref "R14") (pin "1") (pinfunction "1_1") (pintype "passive"))
    )
    (net (code "50") (name "Net-(IC6-Pad1)") (class "Default")
      (node (ref "IC6") (pin "1") (pinfunction "1_1") (pintype "passive"))
      (node (ref "R21") (pin "1") (pinfunction "1_1") (pintype "passive"))
    )
    (net (code "51") (name "Net-(IC6-Pad3)") (class "Default")
      (node (ref "IC6") (pin "3") (pinfunction "3_3") (pintype "passive"))
      (node (ref "R18") (pin "1") (pinfunction "1_1") (pintype "passive"))
    )
    (net (code "52") (name "Net-(IC7-Pad1)") (class "Default")
      (node (ref "IC7") (pin "1") (pinfunction "1_1") (pintype "passive"))
      (node (ref "R25") (pin "1") (pinfunction "1_1") (pintype "passive"))
    )
    (net (code "53") (name "Net-(IC7-Pad3)") (class "Default")
      (node (ref "IC7") (pin "3") (pinfunction "3_3") (pintype "passive"))
      (node (ref "R22") (pin "1") (pinfunction "1_1") (pintype "passive"))
    )
    (net (code "54") (name "Net-(IC8-Pad1)") (class "Default")
      (node (ref "IC8") (pin "1") (pinfunction "1_1") (pintype "passive"))
      (node (ref "R29") (pin "1") (pinfunction "1_1") (pintype "passive"))
    )
    (net (code "55") (name "Net-(IC8-Pad3)") (class "Default")
      (node (ref "IC8") (pin "3") (pinfunction "3_3") (pintype "passive"))
      (node (ref "R26") (pin "1") (pinfunction "1_1") (pintype "passive"))
    )
    (net (code "56") (name "Net-(IC9-Pad1)") (class "Default")
      (node (ref "IC9") (pin "1") (pinfunction "1_1") (pintype "passive"))
      (node (ref "R33") (pin "1") (pinfunction "1_1") (pintype "passive"))
    )
    (net (code "57") (name "Net-(IC9-Pad3)") (class "Default")
      (node (ref "IC9") (pin "3") (pinfunction "3_3") (pintype "passive"))
      (node (ref "R30") (pin "1") (pinfunction "1_1") (pintype "passive"))
    )
    (net (code "58") (name "Net-(IC10-Pad1)") (class "Default")
      (node (ref "IC10") (pin "1") (pinfunction "1_1") (pintype "passive"))
      (node (ref "R37") (pin "1") (pinfunction "1_1") (pintype "passive"))
    )
    (net (code "59") (name "Net-(IC10-Pad3)") (class "Default")
      (node (ref "IC10") (pin "3") (pinfunction "3_3") (pintype "passive"))
      (node (ref "R34") (pin "1") (pinfunction "1_1") (pintype "passive"))
    )
    (net (code "60") (name "Net-(IC11-Pad1)") (class "Default")
      (node (ref "IC11") (pin "1") (pinfunction "1_1") (pintype "passive"))
      (node (ref "R43") (pin "1") (pinfunction "1_1") (pintype "passive"))
    )
    (net (code "61") (name "Net-(IC11-Pad3)") (class "Default")
      (node (ref "IC11") (pin "3") (pinfunction "3_3") (pintype "passive"))
      (node (ref "R40") (pin "1") (pinfunction "1_1") (pintype "passive"))
    )
    (net (code "62") (name "Net-(IC12-Pad1)") (class "Default")
      (node (ref "IC12") (pin "1") (pinfunction "1_1") (pintype "passive"))
      (node (ref "R47") (pin "1") (pinfunction "1_1") (pintype "passive"))
    )
    (net (code "63") (name "Net-(IC12-Pad3)") (class "Default")
      (node (ref "IC12") (pin "3") (pinfunction "3_3") (pintype "passive"))
      (node (ref "R44") (pin "1") (pinfunction "1_1") (pintype "passive"))
    )
    (net (code "64") (name "Net-(IC13-Pad1)") (class "Default")
      (node (ref "IC13") (pin "1") (pinfunction "1_1") (pintype "passive"))
      (node (ref "R51") (pin "1") (pinfunction "1_1") (pintype "passive"))
    )
    (net (code "65") (name "Net-(IC13-Pad3)") (class "Default")
      (node (ref "IC13") (pin "3") (pinfunction "3_3") (pintype "passive"))
      (node (ref "R48") (pin "1") (pinfunction "1_1") (pintype "passive"))
    )
    (net (code "66") (name "Net-(IC14-Pad1)") (class "Default")
      (node (ref "IC14") (pin "1") (pinfunction "1_1") (pintype "passive"))
      (node (ref "R59") (pin "1") (pinfunction "1_1") (pintype "passive"))
    )
    (net (code "67") (name "Net-(IC14-Pad3)") (class "Default")
      (node (ref "IC14") (pin "3") (pinfunction "3_3") (pintype "passive"))
      (node (ref "SV1") (pin "15") (pinfunction "15_15") (pintype "passive"))
    )
    (net (code "68") (name "Net-(LED1-PadC)") (class "Default")
      (node (ref "LED1") (pin "C") (pinfunction "C_C") (pintype "passive"))
      (node (ref "LED2") (pin "A") (pinfunction "A_A") (pintype "passive"))
      (node (ref "R3") (pin "2") (pinfunction "2_2") (pintype "passive"))
      (node (ref "R4") (pin "2") (pinfunction "2_2") (pintype "passive"))
    )
    (net (code "69") (name "Net-(LED3-PadC)") (class "Default")
      (node (ref "LED3") (pin "C") (pinfunction "C_C") (pintype "passive"))
      (node (ref "LED4") (pin "A") (pinfunction "A_A") (pintype "passive"))
      (node (ref "R8") (pin "2") (pinfunction "2_2") (pintype "passive"))
      (node (ref "R9") (pin "2") (pinfunction "2_2") (pintype "passive"))
    )
    (net (code "70") (name "Net-(LED5-PadC)") (class "Default")
      (node (ref "LED5") (pin "C") (pinfunction "C_C") (pintype "passive"))
      (node (ref "LED6") (pin "A") (pinfunction "A_A") (pintype "passive"))
      (node (ref "R11") (pin "2") (pinfunction "2_2") (pintype "passive"))
      (node (ref "R12") (pin "2") (pinfunction "2_2") (pintype "passive"))
    )
    (net (code "71") (name "Net-(LED7-PadC)") (class "Default")
      (node (ref "LED7") (pin "C") (pinfunction "C_C") (pintype "passive"))
      (node (ref "LED8") (pin "A") (pinfunction "A_A") (pintype "passive"))
      (node (ref "R15") (pin "2") (pinfunction "2_2") (pintype "passive"))
      (node (ref "R16") (pin "2") (pinfunction "2_2") (pintype "passive"))
    )
    (net (code "72") (name "Net-(LED10-PadA)") (class "Default")
      (node (ref "LED10") (pin "A") (pinfunction "A_A") (pintype "passive"))
      (node (ref "LED9") (pin "C") (pinfunction "C_C") (pintype "passive"))
      (node (ref "R19") (pin "2") (pinfunction "2_2") (pintype "passive"))
      (node (ref "R20") (pin "2") (pinfunction "2_2") (pintype "passive"))
    )
    (net (code "73") (name "Net-(LED11-PadC)") (class "Default")
      (node (ref "LED11") (pin "C") (pinfunction "C_C") (pintype "passive"))
      (node (ref "LED12") (pin "A") (pinfunction "A_A") (pintype "passive"))
      (node (ref "R23") (pin "2") (pinfunction "2_2") (pintype "passive"))
      (node (ref "R24") (pin "2") (pinfunction "2_2") (pintype "passive"))
    )
    (net (code "74") (name "Net-(LED13-PadC)") (class "Default")
      (node (ref "LED13") (pin "C") (pinfunction "C_C") (pintype "passive"))
      (node (ref "LED14") (pin "A") (pinfunction "A_A") (pintype "passive"))
      (node (ref "R27") (pin "2") (pinfunction "2_2") (pintype "passive"))
      (node (ref "R28") (pin "2") (pinfunction "2_2") (pintype "passive"))
    )
    (net (code "75") (name "Net-(LED15-PadC)") (class "Default")
      (node (ref "LED15") (pin "C") (pinfunction "C_C") (pintype "passive"))
      (node (ref "LED16") (pin "A") (pinfunction "A_A") (pintype "passive"))
      (node (ref "R31") (pin "2") (pinfunction "2_2") (pintype "passive"))
      (node (ref "R32") (pin "2") (pinfunction "2_2") (pintype "passive"))
    )
    (net (code "76") (name "Net-(LED17-PadC)") (class "Default")
      (node (ref "LED17") (pin "C") (pinfunction "C_C") (pintype "passive"))
      (node (ref "LED18") (pin "A") (pinfunction "A_A") (pintype "passive"))
      (node (ref "R35") (pin "2") (pinfunction "2_2") (pintype "passive"))
      (node (ref "R36") (pin "2") (pinfunction "2_2") (pintype "passive"))
    )
    (net (code "77") (name "Net-(LED19-PadC)") (class "Default")
      (node (ref "LED19") (pin "C") (pinfunction "C_C") (pintype "passive"))
      (node (ref "LED20") (pin "A") (pinfunction "A_A") (pintype "passive"))
      (node (ref "R41") (pin "2") (pinfunction "2_2") (pintype "passive"))
      (node (ref "R42") (pin "2") (pinfunction "2_2") (pintype "passive"))
    )
    (net (code "78") (name "Net-(LED21-PadC)") (class "Default")
      (node (ref "LED21") (pin "C") (pinfunction "C_C") (pintype "passive"))
      (node (ref "LED22") (pin "A") (pinfunction "A_A") (pintype "passive"))
      (node (ref "R45") (pin "2") (pinfunction "2_2") (pintype "passive"))
      (node (ref "R46") (pin "2") (pinfunction "2_2") (pintype "passive"))
    )
    (net (code "79") (name "Net-(LED23-PadC)") (class "Default")
      (node (ref "LED23") (pin "C") (pinfunction "C_C") (pintype "passive"))
      (node (ref "LED24") (pin "A") (pinfunction "A_A") (pintype "passive"))
      (node (ref "R49") (pin "2") (pinfunction "2_2") (pintype "passive"))
      (node (ref "R50") (pin "2") (pinfunction "2_2") (pintype "passive"))
    )
    (net (code "80") (name "Net-(R38-S)") (class "Default")
      (node (ref "IC14") (pin "4") (pinfunction "4_4") (pintype "passive"))
      (node (ref "R38") (pin "2") (pinfunction "S_2") (pintype "passive"))
    )
    (net (code "81") (name "Net-(R39-S)") (class "Default")
      (node (ref "R39") (pin "2") (pinfunction "S_2") (pintype "passive"))
      (node (ref "SV1") (pin "3") (pinfunction "3_3") (pintype "passive"))
    )
    (net (code "82") (name "Net-(X6A-S)") (class "Default")
      (node (ref "R40") (pin "2") (pinfunction "2_2") (pintype "passive"))
      (node (ref "X6") (pin "1") (pinfunction "S_1") (pintype "passive"))
    )
    (net (code "83") (name "Net-(X6C-S)") (class "Default")
      (node (ref "IC11") (pin "4") (pinfunction "4_4") (pintype "passive"))
      (node (ref "X6") (pin "2") (pinfunction "S_2") (pintype "passive"))
    )
    (net (code "84") (name "Net-(X6D-S)") (class "Default")
      (node (ref "R44") (pin "2") (pinfunction "2_2") (pintype "passive"))
      (node (ref "X6") (pin "3") (pinfunction "S_3") (pintype "passive"))
    )
    (net (code "85") (name "Net-(X6E-S)") (class "Default")
      (node (ref "IC12") (pin "4") (pinfunction "4_4") (pintype "passive"))
      (node (ref "X6") (pin "4") (pinfunction "S_4") (pintype "passive"))
    )
    (net (code "86") (name "Net-(X6F-S)") (class "Default")
      (node (ref "R48") (pin "2") (pinfunction "2_2") (pintype "passive"))
      (node (ref "X6") (pin "5") (pinfunction "S_5") (pintype "passive"))
    )
    (net (code "87") (name "Net-(X6G-S)") (class "Default")
      (node (ref "IC13") (pin "4") (pinfunction "4_4") (pintype "passive"))
      (node (ref "X6") (pin "6") (pinfunction "S_6") (pintype "passive"))
    )
    (net (code "88") (name "Net-(X8B-S)") (class "Default")
      (node (ref "R14") (pin "2") (pinfunction "2_2") (pintype "passive"))
      (node (ref "X8") (pin "10") (pinfunction "S_10") (pintype "passive"))
    )
    (net (code "89") (name "Net-(X8D-S)") (class "Default")
      (node (ref "IC2") (pin "4") (pinfunction "4_4") (pintype "passive"))
      (node (ref "X8") (pin "3") (pinfunction "S_3") (pintype "passive"))
    )
    (net (code "90") (name "Net-(X8E-S)") (class "Default")
      (node (ref "R2") (pin "2") (pinfunction "2_2") (pintype "passive"))
      (node (ref "X8") (pin "4") (pinfunction "S_4") (pintype "passive"))
    )
    (net (code "91") (name "Net-(X8F-S)") (class "Default")
      (node (ref "IC3") (pin "4") (pinfunction "4_4") (pintype "passive"))
      (node (ref "X8") (pin "5") (pinfunction "S_5") (pintype "passive"))
    )
    (net (code "92") (name "Net-(X8G-S)") (class "Default")
      (node (ref "R7") (pin "2") (pinfunction "2_2") (pintype "passive"))
      (node (ref "X8") (pin "6") (pinfunction "S_6") (pintype "passive"))
    )
    (net (code "93") (name "Net-(X8H-S)") (class "Default")
      (node (ref "IC4") (pin "4") (pinfunction "4_4") (pintype "passive"))
      (node (ref "X8") (pin "7") (pinfunction "S_7") (pintype "passive"))
    )
    (net (code "94") (name "Net-(X8I-S)") (class "Default")
      (node (ref "R6") (pin "2") (pinfunction "2_2") (pintype "passive"))
      (node (ref "X8") (pin "8") (pinfunction "S_8") (pintype "passive"))
    )
    (net (code "95") (name "Net-(X8J-S)") (class "Default")
      (node (ref "IC5") (pin "4") (pinfunction "4_4") (pintype "passive"))
      (node (ref "X8") (pin "9") (pinfunction "S_9") (pintype "passive"))
    )
    (net (code "96") (name "Net-(X9A-S)") (class "Default")
      (node (ref "IC6") (pin "4") (pinfunction "4_4") (pintype "passive"))
      (node (ref "X9") (pin "1") (pinfunction "S_1") (pintype "passive"))
    )
    (net (code "97") (name "Net-(X9B-S)") (class "Default")
      (node (ref "R34") (pin "2") (pinfunction "2_2") (pintype "passive"))
      (node (ref "X9") (pin "10") (pinfunction "S_10") (pintype "passive"))
    )
    (net (code "98") (name "Net-(X9C-S)") (class "Default")
      (node (ref "R18") (pin "2") (pinfunction "2_2") (pintype "passive"))
      (node (ref "X9") (pin "2") (pinfunction "S_2") (pintype "passive"))
    )
    (net (code "99") (name "Net-(X9D-S)") (class "Default")
      (node (ref "IC7") (pin "4") (pinfunction "4_4") (pintype "passive"))
      (node (ref "X9") (pin "3") (pinfunction "S_3") (pintype "passive"))
    )
    (net (code "100") (name "Net-(X9E-S)") (class "Default")
      (node (ref "R22") (pin "2") (pinfunction "2_2") (pintype "passive"))
      (node (ref "X9") (pin "4") (pinfunction "S_4") (pintype "passive"))
    )
    (net (code "101") (name "Net-(X9F-S)") (class "Default")
      (node (ref "IC8") (pin "4") (pinfunction "4_4") (pintype "passive"))
      (node (ref "X9") (pin "5") (pinfunction "S_5") (pintype "passive"))
    )
    (net (code "102") (name "Net-(X9G-S)") (class "Default")
      (node (ref "R26") (pin "2") (pinfunction "2_2") (pintype "passive"))
      (node (ref "X9") (pin "6") (pinfunction "S_6") (pintype "passive"))
    )
    (net (code "103") (name "Net-(X9H-S)") (class "Default")
      (node (ref "IC9") (pin "4") (pinfunction "4_4") (pintype "passive"))
      (node (ref "X9") (pin "7") (pinfunction "S_7") (pintype "passive"))
    )
    (net (code "104") (name "Net-(X9I-S)") (class "Default")
      (node (ref "R30") (pin "2") (pinfunction "2_2") (pintype "passive"))
      (node (ref "X9") (pin "8") (pinfunction "S_8") (pintype "passive"))
    )
    (net (code "105") (name "Net-(X9J-S)") (class "Default")
      (node (ref "IC10") (pin "4") (pinfunction "4_4") (pintype "passive"))
      (node (ref "X9") (pin "9") (pinfunction "S_9") (pintype "passive"))
    )
    (net (code "106") (name "VDD") (class "Default")
      (node (ref "C2") (pin "2") (pinfunction "2_2") (pintype "passive"))
      (node (ref "C3") (pin "2") (pinfunction "2_2") (pintype "passive"))
      (node (ref "C4") (pin "2") (pinfunction "2_2") (pintype "passive"))
      (node (ref "IC1") (pin "17") (pinfunction "AVDD_17") (pintype "power_in"))
      (node (ref "IC1") (pin "28") (pinfunction "VDD_28") (pintype "power_in"))
      (node (ref "IC1") (pin "40") (pinfunction "VDD_40") (pintype "power_in"))
      (node (ref "R1") (pin "1") (pinfunction "1_1") (pintype "passive"))
      (node (ref "R38") (pin "3") (pinfunction "E_3") (pintype "passive"))
      (node (ref "R39") (pin "1") (pinfunction "A_1") (pintype "passive"))
      (node (ref "SV1") (pin "2") (pinfunction "2_2") (pintype "passive"))
      (node (ref "SV3") (pin "2") (pinfunction "2_2") (pintype "passive"))
      (node (ref "X8") (pin "1") (pinfunction "S_1") (pintype "passive"))
    )
    (net (code "107") (name "VSS") (class "Default")
      (node (ref "C1") (pin "1") (pinfunction "1_1") (pintype "passive"))
      (node (ref "C10") (pin "1") (pinfunction "1_1") (pintype "passive"))
      (node (ref "C11") (pin "1") (pinfunction "1_1") (pintype "passive"))
      (node (ref "C12") (pin "1") (pinfunction "1_1") (pintype "passive"))
      (node (ref "C13") (pin "1") (pinfunction "1_1") (pintype "passive"))
      (node (ref "C2") (pin "1") (pinfunction "1_1") (pintype "passive"))
      (node (ref "C3") (pin "1") (pinfunction "1_1") (pintype "passive"))
      (node (ref "C4") (pin "1") (pinfunction "1_1") (pintype "passive"))
      (node (ref "C5") (pin "1") (pinfunction "1_1") (pintype "passive"))
      (node (ref "C6") (pin "1") (pinfunction "1_1") (pintype "passive"))
      (node (ref "C7") (pin "1") (pinfunction "1_1") (pintype "passive"))
      (node (ref "C8") (pin "1") (pinfunction "1_1") (pintype "passive"))
      (node (ref "C9") (pin "1") (pinfunction "1_1") (pintype "passive"))
      (node (ref "D1") (pin "2") (pinfunction "A_2") (pintype "passive"))
      (node (ref "D2") (pin "2") (pinfunction "A_2") (pintype "passive"))
      (node (ref "D3") (pin "2") (pinfunction "A_2") (pintype "passive"))
      (node (ref "D4") (pin "2") (pinfunction "A_2") (pintype "passive"))
      (node (ref "D5") (pin "2") (pinfunction "A_2") (pintype "passive"))
      (node (ref "D6") (pin "2") (pinfunction "A_2") (pintype "passive"))
      (node (ref "D7") (pin "2") (pinfunction "A_2") (pintype "passive"))
      (node (ref "IC1") (pin "16") (pinfunction "AVSS_16") (pintype "power_in"))
      (node (ref "IC1") (pin "29") (pinfunction "VSS_29") (pintype "power_in"))
      (node (ref "IC1") (pin "39") (pinfunction "VSS_39") (pintype "power_in"))
      (node (ref "IC10") (pin "2") (pinfunction "2_2") (pintype "passive"))
      (node (ref "IC11") (pin "2") (pinfunction "2_2") (pintype "passive"))
      (node (ref "IC12") (pin "2") (pinfunction "2_2") (pintype "passive"))
      (node (ref "IC13") (pin "2") (pinfunction "2_2") (pintype "passive"))
      (node (ref "IC14") (pin "2") (pinfunction "2_2") (pintype "passive"))
      (node (ref "IC2") (pin "2") (pinfunction "2_2") (pintype "passive"))
      (node (ref "IC3") (pin "2") (pinfunction "2_2") (pintype "passive"))
      (node (ref "IC4") (pin "2") (pinfunction "2_2") (pintype "passive"))
      (node (ref "IC5") (pin "2") (pinfunction "2_2") (pintype "passive"))
      (node (ref "IC6") (pin "2") (pinfunction "2_2") (pintype "passive"))
      (node (ref "IC7") (pin "2") (pinfunction "2_2") (pintype "passive"))
      (node (ref "IC8") (pin "2") (pinfunction "2_2") (pintype "passive"))
      (node (ref "IC9") (pin "2") (pinfunction "2_2") (pintype "passive"))
      (node (ref "R12") (pin "1") (pinfunction "1_1") (pintype "passive"))
      (node (ref "R16") (pin "1") (pinfunction "1_1") (pintype "passive"))
      (node (ref "R20") (pin "1") (pinfunction "1_1") (pintype "passive"))
      (node (ref "R24") (pin "1") (pinfunction "1_1") (pintype "passive"))
      (node (ref "R28") (pin "1") (pinfunction "1_1") (pintype "passive"))
      (node (ref "R32") (pin "1") (pinfunction "1_1") (pintype "passive"))
      (node (ref "R36") (pin "1") (pinfunction "1_1") (pintype "passive"))
      (node (ref "R38") (pin "1") (pinfunction "A_1") (pintype "passive"))
      (node (ref "R39") (pin "3") (pinfunction "E_3") (pintype "passive"))
      (node (ref "R4") (pin "1") (pinfunction "1_1") (pintype "passive"))
      (node (ref "R42") (pin "1") (pinfunction "1_1") (pintype "passive"))
      (node (ref "R46") (pin "1") (pinfunction "1_1") (pintype "passive"))
      (node (ref "R50") (pin "1") (pinfunction "1_1") (pintype "passive"))
      (node (ref "R52") (pin "1") (pinfunction "1_1") (pintype "passive"))
      (node (ref "R53") (pin "1") (pinfunction "1_1") (pintype "passive"))
      (node (ref "R54") (pin "1") (pinfunction "1_1") (pintype "passive"))
      (node (ref "R55") (pin "1") (pinfunction "1_1") (pintype "passive"))
      (node (ref "R56") (pin "1") (pinfunction "1_1") (pintype "passive"))
      (node (ref "R57") (pin "1") (pinfunction "1_1") (pintype "passive"))
      (node (ref "R58") (pin "1") (pinfunction "1_1") (pintype "passive"))
      (node (ref "R9") (pin "1") (pinfunction "1_1") (pintype "passive"))
      (node (ref "SV1") (pin "1") (pinfunction "1_1") (pintype "passive"))
      (node (ref "SV1") (pin "10") (pinfunction "10_10") (pintype "passive"))
      (node (ref "SV1") (pin "16") (pinfunction "16_16") (pintype "passive"))
      (node (ref "SV1") (pin "5") (pinfunction "5_5") (pintype "passive"))
      (node (ref "SV1") (pin "7") (pinfunction "7_7") (pintype "passive"))
      (node (ref "SV1") (pin "8") (pinfunction "8_8") (pintype "passive"))
      (node (ref "SV1") (pin "9") (pinfunction "9_9") (pintype "passive"))
      (node (ref "SV3") (pin "3") (pinfunction "3_3") (pintype "passive"))
      (node (ref "X6") (pin "7") (pinfunction "S_7") (pintype "passive"))
      (node (ref "X6") (pin "9") (pinfunction "S_9") (pintype "passive"))
      (node (ref "X7") (pin "1") (pinfunction "S_1") (pintype "passive"))
      (node (ref "X7") (pin "3") (pinfunction "S_3") (pintype "passive"))
      (node (ref "X7") (pin "5") (pinfunction "S_5") (pintype "passive"))
      (node (ref "X7") (pin "7") (pinfunction "S_7") (pintype "passive"))
      (node (ref "X7") (pin "9") (pinfunction "S_9") (pintype "passive"))
      (node (ref "X8") (pin "2") (pinfunction "S_2") (pintype "passive"))
    )
    (net (code "108") (name "unconnected-(SV3-Pad6)") (class "Default")
      (node (ref "SV3") (pin "6") (pinfunction "6_6") (pintype "passive"))
    )
  )
)
